# VIDCEnhancer.net
KiCad netlist of a schematic drawn in Altium Designer
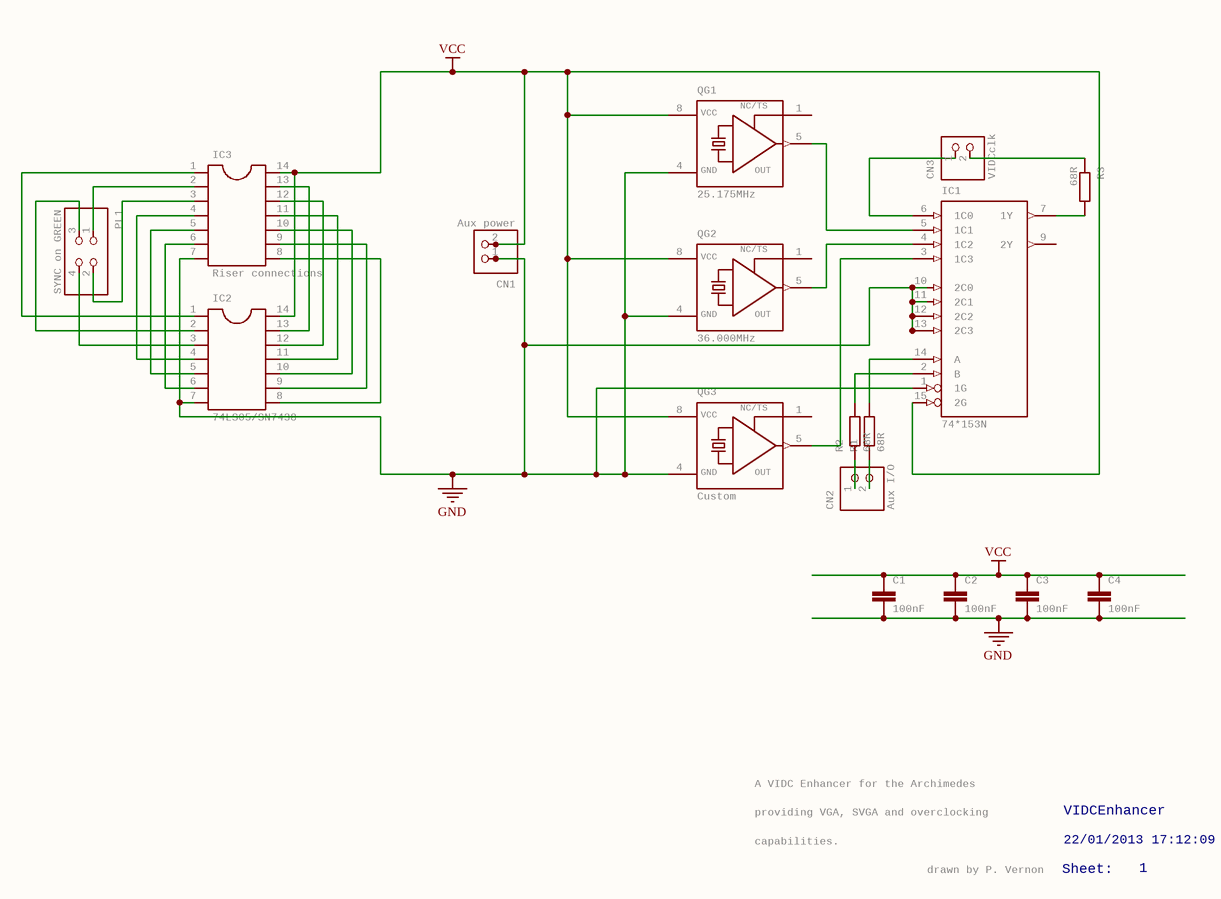
[diagram p0: VIDCEnhancer.SchDoc]

(export (version "E")
  (design (tool "Eeschema 10.0.6"))
  (components
    (comp (ref "C1")
      (value "100nF")
      (footprint "C025-025X050")
      (description "CAPACITOR, European symbol")
      (libsource (lib "rcl") (part "C-EU025-025X050"))
    )
    (comp (ref "C2")
      (value "100nF")
      (footprint "C025-025X050")
      (description "CAPACITOR, European symbol")
      (libsource (lib "rcl") (part "C-EU025-025X050"))
    )
    (comp (ref "C3")
      (value "100nF")
      (footprint "C025-025X050")
      (description "CAPACITOR, European symbol")
      (libsource (lib "rcl") (part "C-EU025-025X050"))
    )
    (comp (ref "C4")
      (value "100nF")
      (footprint "C025-025X050")
      (description "CAPACITOR, European symbol")
      (libsource (lib "rcl") (part "C-EU025-025X050"))
    )
    (comp (ref "CN1")
      (value "Aux power")
      (footprint "1X02/90")
      (description "PIN HEADER")
      (fields (field (name "LIBRARYNAME") "pinhead"))
      (libsource (lib "pinhead") (part "PINHD-1X2/90"))
    )
    (comp (ref "CN2")
      (value "Aux I/O")
      (footprint "1X02/90")
      (description "PIN HEADER")
      (fields (field (name "LIBRARYNAME") "pinhead"))
      (libsource (lib "pinhead") (part "PINHD-1X2/90"))
    )
    (comp (ref "CN3")
      (value "VIDCclk")
      (footprint "1X02/90")
      (description "PIN HEADER")
      (fields (field (name "LIBRARYNAME") "pinhead"))
      (libsource (lib "pinhead") (part "PINHD-1X2/90"))
    )
    (comp (ref "IC1")
      (value "74*153N")
      (footprint "DIL16")
      (description "Dual 4-line to 1-line data SELECTOR/MULTIPLEXER")
      (libsource (lib "74xx-eu") (part "74*153N"))
    )
    (comp (ref "IC2")
      (value "74LS05/SN7438")
      (footprint "SOCKET-14")
      (description "Dual In Line / Socket")
      (libsource (lib "ic-package") (part "DIL14S"))
    )
    (comp (ref "IC3")
      (value "Riser connections")
      (footprint "SOCKET-14")
      (description "Dual In Line / Socket")
      (libsource (lib "ic-package") (part "DIL14S"))
    )
    (comp (ref "PL1")
      (value "SYNC on GREEN")
      (footprint "2X02")
      (description "PIN HEADER")
      (fields (field (name "LIBRARYNAME") "pinhead"))
      (libsource (lib "pinhead") (part "PINHD-2X2"))
    )
    (comp (ref "QG1")
      (value "25.175MHz")
      (footprint "DIL08S")
      (description "CRYSTAL")
      (fields
        (field (name "OUT") "OUT")
        (field (name "GND") "GND")
        (field (name "VCC") "VCC")
        (field (name "NC/TS") "NC/TS")
        (field (name "MF") "MF")
        (field (name "MPN") "MPN")
      )
      (libsource (lib "crystal") (part "XO-8"))
    )
    (comp (ref "QG2")
      (value "36.000MHz")
      (footprint "DIL08S")
      (description "CRYSTAL")
      (fields
        (field (name "OUT") "OUT")
        (field (name "GND") "GND")
        (field (name "VCC") "VCC")
        (field (name "NC/TS") "NC/TS")
        (field (name "MF") "MF")
        (field (name "MPN") "MPN")
      )
      (libsource (lib "crystal") (part "XO-8"))
    )
    (comp (ref "QG3")
      (value "Custom")
      (footprint "DIL08S")
      (description "CRYSTAL")
      (fields
        (field (name "OUT") "OUT")
        (field (name "GND") "GND")
        (field (name "VCC") "VCC")
        (field (name "NC/TS") "NC/TS")
        (field (name "MF") "MF")
        (field (name "MPN") "MPN")
      )
      (libsource (lib "crystal") (part "XO-8"))
    )
    (comp (ref "R1")
      (value "68R")
      (footprint "0207/10")
      (description "RESISTOR, European symbol")
      (libsource (lib "resistor") (part "R-EU_0207/10"))
    )
    (comp (ref "R2")
      (value "68R")
      (footprint "0207/10")
      (description "RESISTOR, European symbol")
      (libsource (lib "resistor") (part "R-EU_0207/10"))
    )
    (comp (ref "R3")
      (value "68R")
      (footprint "0207/10")
      (description "RESISTOR, European symbol")
      (libsource (lib "resistor") (part "R-EU_0207/10"))
    )
  )
  (nets
    (net (code "1") (name "GND") (class "Default")
      (node (ref "C1") (pin "2") (pinfunction "2_2") (pintype "passive"))
      (node (ref "C2") (pin "2") (pinfunction "2_2") (pintype "passive"))
      (node (ref "C3") (pin "2") (pinfunction "2_2") (pintype "passive"))
      (node (ref "C4") (pin "2") (pinfunction "2_2") (pintype "passive"))
      (node (ref "CN1") (pin "1") (pinfunction "1_1") (pintype "passive"))
      (node (ref "IC1") (pin "1") (pinfunction "1G_1") (pintype "input"))
      (node (ref "IC1") (pin "10") (pinfunction "2C0_10") (pintype "input"))
      (node (ref "IC1") (pin "11") (pinfunction "2C1_11") (pintype "input"))
      (node (ref "IC1") (pin "12") (pinfunction "2C2_12") (pintype "input"))
      (node (ref "IC1") (pin "13") (pinfunction "2C3_13") (pintype "input"))
      (node (ref "IC2") (pin "7") (pinfunction "7_7") (pintype "passive"))
      (node (ref "IC3") (pin "7") (pinfunction "7_7") (pintype "passive"))
      (node (ref "QG1") (pin "4") (pinfunction "GND_4") (pintype "power_in"))
      (node (ref "QG2") (pin "4") (pinfunction "GND_4") (pintype "power_in"))
      (node (ref "QG3") (pin "4") (pinfunction "GND_4") (pintype "power_in"))
    )
    (net (code "2") (name "Net-(CN2-Pad1)") (class "Default")
      (node (ref "CN2") (pin "1") (pinfunction "1_1") (pintype "passive"))
      (node (ref "R2") (pin "1") (pinfunction "1_1") (pintype "passive"))
    )
    (net (code "3") (name "Net-(CN2-Pad2)") (class "Default")
      (node (ref "CN2") (pin "2") (pinfunction "2_2") (pintype "passive"))
      (node (ref "R1") (pin "1") (pinfunction "1_1") (pintype "passive"))
    )
    (net (code "4") (name "Net-(CN3-Pad2)") (class "Default")
      (node (ref "CN3") (pin "2") (pinfunction "2_2") (pintype "passive"))
      (node (ref "R3") (pin "1") (pinfunction "1_1") (pintype "passive"))
    )
    (net (code "5") (name "Net-(IC1-1C0)") (class "Default")
      (node (ref "CN3") (pin "1") (pinfunction "1_1") (pintype "passive"))
      (node (ref "IC1") (pin "6") (pinfunction "1C0_6") (pintype "input"))
    )
    (net (code "6") (name "Net-(IC1-1C1)") (class "Default")
      (node (ref "IC1") (pin "5") (pinfunction "1C1_5") (pintype "input"))
      (node (ref "QG1") (pin "5") (pinfunction "OUT_5") (pintype "output"))
    )
    (net (code "7") (name "Net-(IC1-1C2)") (class "Default")
      (node (ref "IC1") (pin "4") (pinfunction "1C2_4") (pintype "input"))
      (node (ref "QG2") (pin "5") (pinfunction "OUT_5") (pintype "output"))
    )
    (net (code "8") (name "Net-(IC1-1C3)") (class "Default")
      (node (ref "IC1") (pin "3") (pinfunction "1C3_3") (pintype "input"))
      (node (ref "QG3") (pin "5") (pinfunction "OUT_5") (pintype "output"))
    )
    (net (code "9") (name "Net-(IC1-1Y)") (class "Default")
      (node (ref "IC1") (pin "7") (pinfunction "1Y_7") (pintype "output"))
      (node (ref "R3") (pin "2") (pinfunction "2_2") (pintype "passive"))
    )
    (net (code "10") (name "Net-(IC1-A)") (class "Default")
      (node (ref "IC1") (pin "14") (pinfunction "A_14") (pintype "input"))
      (node (ref "R1") (pin "2") (pinfunction "2_2") (pintype "passive"))
    )
    (net (code "11") (name "Net-(IC1-B)") (class "Default")
      (node (ref "IC1") (pin "2") (pinfunction "B_2") (pintype "input"))
      (node (ref "R2") (pin "2") (pinfunction "2_2") (pintype "passive"))
    )
    (net (code "12") (name "Net-(IC2-Pad1)") (class "Default")
      (node (ref "IC2") (pin "1") (pinfunction "1_1") (pintype "passive"))
      (node (ref "IC3") (pin "1") (pinfunction "1_1") (pintype "passive"))
    )
    (net (code "13") (name "Net-(IC2-Pad2)") (class "Default")
      (node (ref "IC2") (pin "2") (pinfunction "2_2") (pintype "passive"))
      (node (ref "PL1") (pin "3") (pinfunction "3_3") (pintype "passive"))
    )
    (net (code "14") (name "Net-(IC2-Pad3)") (class "Default")
      (node (ref "IC2") (pin "3") (pinfunction "3_3") (pintype "passive"))
      (node (ref "PL1") (pin "4") (pinfunction "4_4") (pintype "passive"))
    )
    (net (code "15") (name "Net-(IC2-Pad4)") (class "Default")
      (node (ref "IC2") (pin "4") (pinfunction "4_4") (pintype "passive"))
      (node (ref "IC3") (pin "4") (pinfunction "4_4") (pintype "passive"))
    )
    (net (code "16") (name "Net-(IC2-Pad5)") (class "Default")
      (node (ref "IC2") (pin "5") (pinfunction "5_5") (pintype "passive"))
      (node (ref "IC3") (pin "5") (pinfunction "5_5") (pintype "passive"))
    )
    (net (code "17") (name "Net-(IC2-Pad6)") (class "Default")
      (node (ref "IC2") (pin "6") (pinfunction "6_6") (pintype "passive"))
      (node (ref "IC3") (pin "6") (pinfunction "6_6") (pintype "passive"))
    )
    (net (code "18") (name "Net-(IC2-Pad8)") (class "Default")
      (node (ref "IC2") (pin "8") (pinfunction "8_8") (pintype "passive"))
      (node (ref "IC3") (pin "8") (pinfunction "8_8") (pintype "passive"))
    )
    (net (code "19") (name "Net-(IC2-Pad9)") (class "Default")
      (node (ref "IC2") (pin "9") (pinfunction "9_9") (pintype "passive"))
      (node (ref "IC3") (pin "9") (pinfunction "9_9") (pintype "passive"))
    )
    (net (code "20") (name "Net-(IC2-Pad10)") (class "Default")
      (node (ref "IC2") (pin "10") (pinfunction "10_10") (pintype "passive"))
      (node (ref "IC3") (pin "10") (pinfunction "10_10") (pintype "passive"))
    )
    (net (code "21") (name "Net-(IC2-Pad11)") (class "Default")
      (node (ref "IC2") (pin "11") (pinfunction "11_11") (pintype "passive"))
      (node (ref "IC3") (pin "11") (pinfunction "11_11") (pintype "passive"))
    )
    (net (code "22") (name "Net-(IC2-Pad12)") (class "Default")
      (node (ref "IC2") (pin "12") (pinfunction "12_12") (pintype "passive"))
      (node (ref "IC3") (pin "12") (pinfunction "12_12") (pintype "passive"))
    )
    (net (code "23") (name "Net-(IC2-Pad13)") (class "Default")
      (node (ref "IC2") (pin "13") (pinfunction "13_13") (pintype "passive"))
      (node (ref "IC3") (pin "13") (pinfunction "13_13") (pintype "passive"))
    )
    (net (code "24") (name "Net-(IC3-Pad2)") (class "Default")
      (node (ref "IC3") (pin "2") (pinfunction "2_2") (pintype "passive"))
      (node (ref "PL1") (pin "1") (pinfunction "1_1") (pintype "passive"))
    )
    (net (code "25") (name "Net-(IC3-Pad3)") (class "Default")
      (node (ref "IC3") (pin "3") (pinfunction "3_3") (pintype "passive"))
      (node (ref "PL1") (pin "2") (pinfunction "2_2") (pintype "passive"))
    )
    (net (code "26") (name "VCC") (class "Default")
      (node (ref "C1") (pin "1") (pinfunction "1_1") (pintype "passive"))
      (node (ref "C2") (pin "1") (pinfunction "1_1") (pintype "passive"))
      (node (ref "C3") (pin "1") (pinfunction "1_1") (pintype "passive"))
      (node (ref "C4") (pin "1") (pinfunction "1_1") (pintype "passive"))
      (node (ref "CN1") (pin "2") (pinfunction "2_2") (pintype "passive"))
      (node (ref "IC1") (pin "15") (pinfunction "2G_15") (pintype "input"))
      (node (ref "IC2") (pin "14") (pinfunction "14_14") (pintype "passive"))
      (node (ref "IC3") (pin "14") (pinfunction "14_14") (pintype "passive"))
      (node (ref "QG1") (pin "8") (pinfunction "VCC_8") (pintype "power_in"))
      (node (ref "QG2") (pin "8") (pinfunction "VCC_8") (pintype "power_in"))
      (node (ref "QG3") (pin "8") (pinfunction "VCC_8") (pintype "power_in"))
    )
    (net (code "27") (name "unconnected-(IC1-2Y-Pad9)") (class "Default")
      (node (ref "IC1") (pin "9") (pinfunction "2Y_9") (pintype "output"))
    )
    (net (code "28") (name "unconnected-(QG1-TS-Pad1)") (class "Default")
      (node (ref "QG1") (pin "1") (pinfunction "TS_1") (pintype "passive"))
    )
    (net (code "29") (name "unconnected-(QG2-TS-Pad1)") (class "Default")
      (node (ref "QG2") (pin "1") (pinfunction "TS_1") (pintype "passive"))
    )
    (net (code "30") (name "unconnected-(QG3-TS-Pad1)") (class "Default")
      (node (ref "QG3") (pin "1") (pinfunction "TS_1") (pintype "passive"))
    )
  )
)
